# Electret_Microphone_Breakout.net
KiCad netlist of a schematic drawn in EAGLE
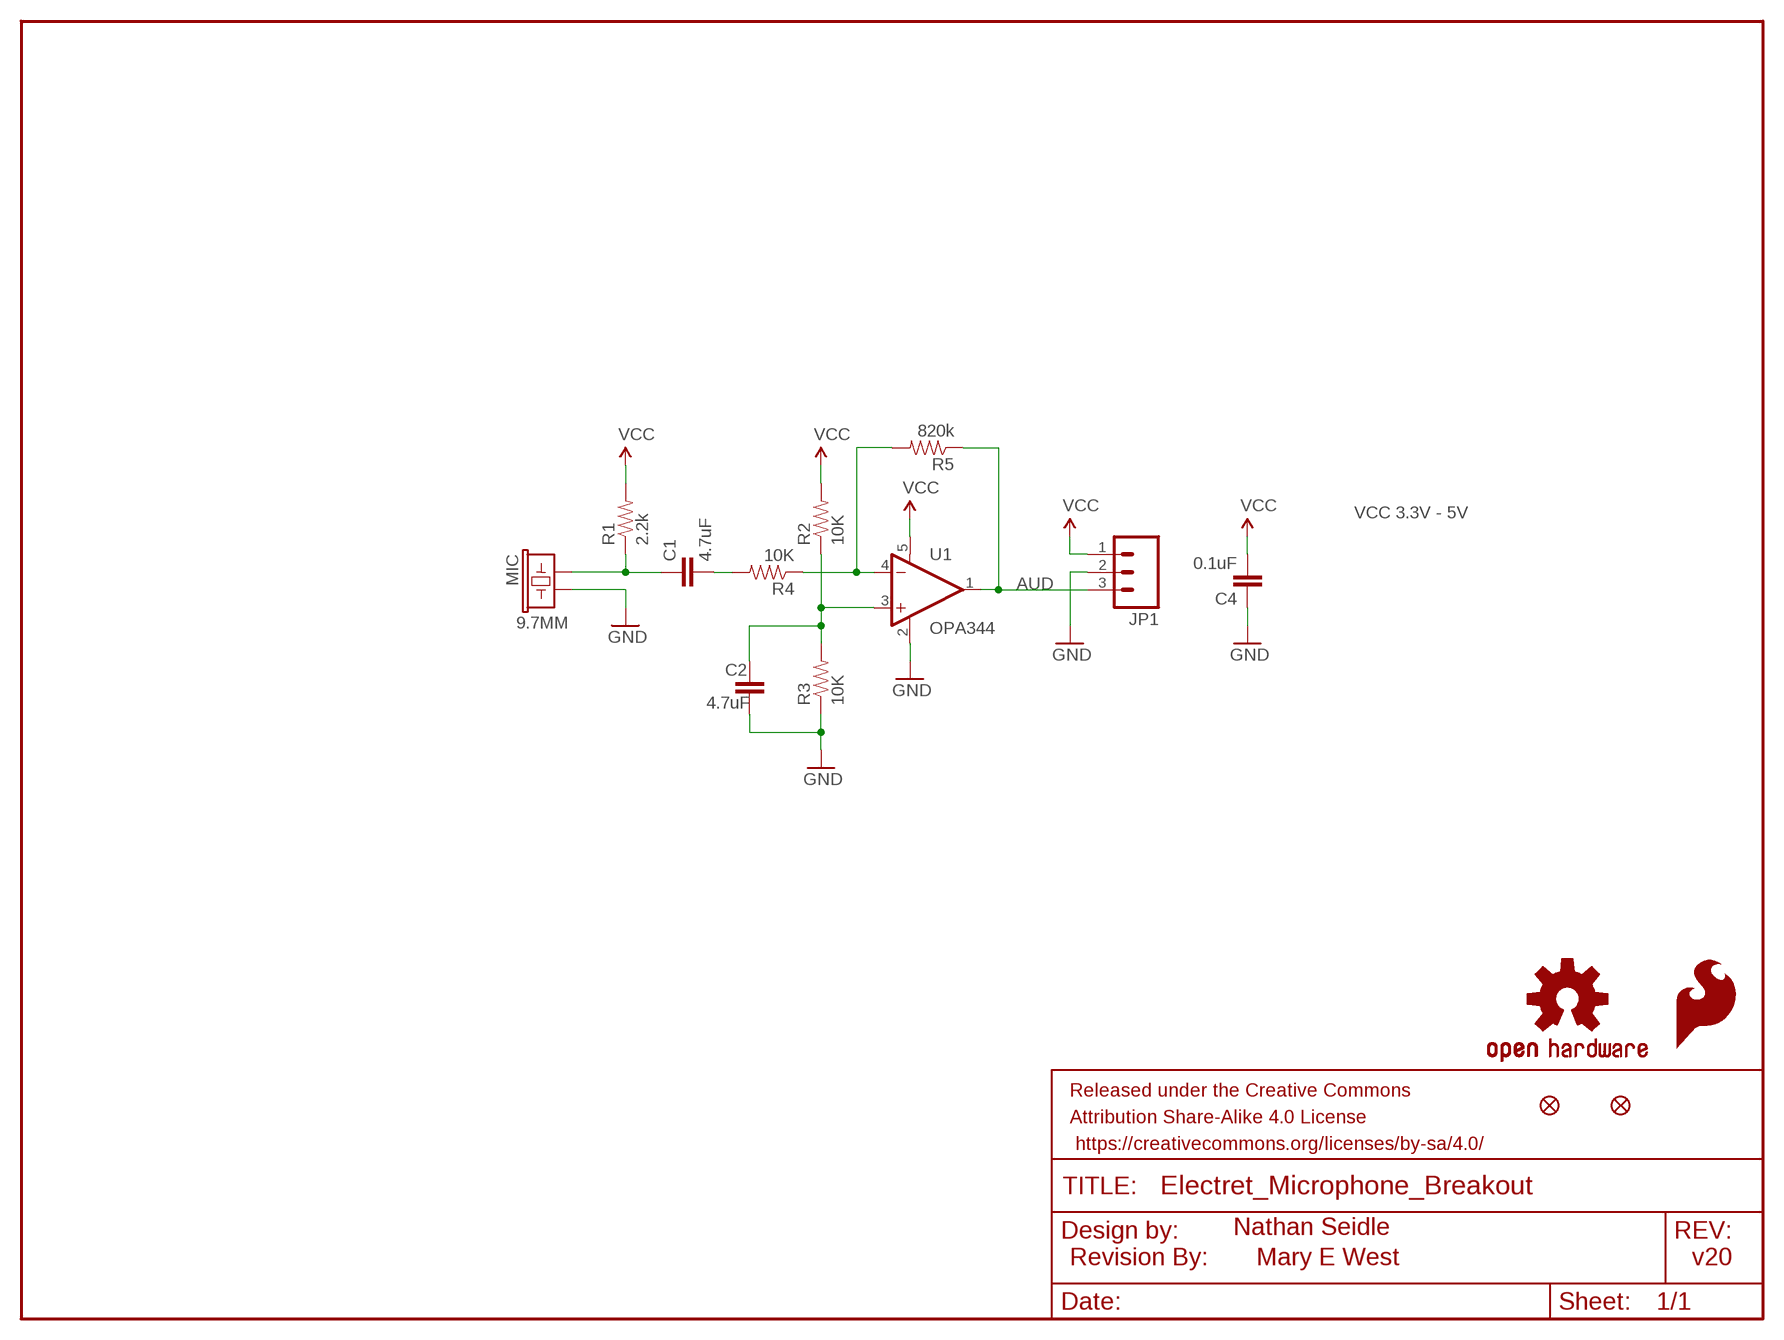
[diagram p0: schematic, sheet 1]

(export (version "E")
  (design (tool "Eeschema 10.0.6"))
  (components
    (comp (ref "C1")
      (value "4.7uF")
      (footprint "eagle-import:0603-CAP")
      (libsource (lib "eagle-import") (part "4.7UF-6.3V-10%(0603)0603"))
    )
    (comp (ref "C2")
      (value "4.7uF")
      (footprint "eagle-import:0603-CAP")
      (libsource (lib "eagle-import") (part "4.7UF-6.3V-10%(0603)0603"))
    )
    (comp (ref "C4")
      (value "0.1uF")
      (footprint "eagle-import:0603-CAP")
      (libsource (lib "eagle-import") (part "0.1UF-25V(+80/-20%)(0603)"))
    )
    (comp (ref "FRAME1")
      (value "FRAME-LETTER")
      (footprint "eagle-import:CREATIVE_COMMONS")
      (libsource (lib "eagle-import") (part "FRAME-LETTER"))
    )
    (comp (ref "JP1")
      (value "M03PTH")
      (footprint "eagle-import:1X03")
      (libsource (lib "eagle-import") (part "M03PTH"))
    )
    (comp (ref "JP2")
      (value "FIDUCIALUFIDUCIAL")
      (footprint "eagle-import:MICRO-FIDUCIAL")
      (libsource (lib "eagle-import") (part "FIDUCIALUFIDUCIAL"))
    )
    (comp (ref "JP3")
      (value "FIDUCIALUFIDUCIAL")
      (footprint "eagle-import:MICRO-FIDUCIAL")
      (libsource (lib "eagle-import") (part "FIDUCIALUFIDUCIAL"))
    )
    (comp (ref "LOGO1")
      (value "OSHW-LOGOMINI")
      (footprint "eagle-import:OSHW-LOGO-MINI")
      (libsource (lib "eagle-import") (part "OSHW-LOGOMINI"))
    )
    (comp (ref "MIC")
      (value "9.7MM")
      (footprint "eagle-import:MIC-9.7MM")
      (libsource (lib "eagle-import") (part "MIC9.7MM"))
    )
    (comp (ref "R1")
      (value "2.2k")
      (footprint "eagle-import:0603-RES")
      (libsource (lib "eagle-import") (part "2.2KOHM-1/10W-1%(0603)"))
    )
    (comp (ref "R2")
      (value "10K")
      (footprint "eagle-import:0603-RES")
      (libsource (lib "eagle-import") (part "10KOHM-1/10W-1%(0603)0603"))
    )
    (comp (ref "R3")
      (value "10K")
      (footprint "eagle-import:0603-RES")
      (libsource (lib "eagle-import") (part "10KOHM-1/10W-1%(0603)0603"))
    )
    (comp (ref "R4")
      (value "10K")
      (footprint "eagle-import:0603-RES")
      (libsource (lib "eagle-import") (part "10KOHM-1/10W-1%(0603)0603"))
    )
    (comp (ref "R5")
      (value "820k")
      (footprint "eagle-import:0603-RES")
      (libsource (lib "eagle-import") (part "820KOHM-1/10W-1%(0603)"))
    )
    (comp (ref "U$1")
      (value "SFE_LOGO_FLAME.1_INCH")
      (footprint "eagle-import:SFE_LOGO_FLAME_.1")
      (libsource (lib "eagle-import") (part "SFE_LOGO_FLAME.1_INCH"))
    )
    (comp (ref "U$2")
      (value "REVISION")
      (footprint "eagle-import:REVISION")
      (libsource (lib "eagle-import") (part "REVISION"))
    )
    (comp (ref "U1")
      (value "OPA344")
      (footprint "eagle-import:SOT23-5")
      (libsource (lib "eagle-import") (part "OPA344"))
    )
  )
  (nets
    (net (code "1") (name "/AUD") (class "Default")
      (node (ref "JP1") (pin "3") (pinfunction "3_3") (pintype "passive"))
      (node (ref "R5") (pin "1") (pinfunction "1_1") (pintype "passive"))
      (node (ref "U1") (pin "1") (pinfunction "OUT_1") (pintype "output"))
    )
    (net (code "2") (name "GND") (class "Default")
      (node (ref "C2") (pin "2") (pinfunction "2_2") (pintype "passive"))
      (node (ref "C4") (pin "1") (pinfunction "1_1") (pintype "passive"))
      (node (ref "JP1") (pin "2") (pinfunction "2_2") (pintype "passive"))
      (node (ref "MIC") (pin "2") (pinfunction "2_2") (pintype "passive"))
      (node (ref "R3") (pin "1") (pinfunction "1_1") (pintype "passive"))
      (node (ref "U1") (pin "2") (pinfunction "V-_2") (pintype "power_in"))
    )
    (net (code "3") (name "Net-(C1-Pad1)") (class "Default")
      (node (ref "C1") (pin "1") (pinfunction "1_1") (pintype "passive"))
      (node (ref "MIC") (pin "1") (pinfunction "1_1") (pintype "passive"))
      (node (ref "R1") (pin "1") (pinfunction "1_1") (pintype "passive"))
    )
    (net (code "4") (name "Net-(C1-Pad2)") (class "Default")
      (node (ref "C1") (pin "2") (pinfunction "2_2") (pintype "passive"))
      (node (ref "R4") (pin "2") (pinfunction "2_2") (pintype "passive"))
    )
    (net (code "5") (name "Net-(U1-+IN)") (class "Default")
      (node (ref "C2") (pin "1") (pinfunction "1_1") (pintype "passive"))
      (node (ref "R2") (pin "1") (pinfunction "1_1") (pintype "passive"))
      (node (ref "R3") (pin "2") (pinfunction "2_2") (pintype "passive"))
      (node (ref "U1") (pin "3") (pinfunction "+IN_3") (pintype "input"))
    )
    (net (code "6") (name "Net-(U1--IN)") (class "Default")
      (node (ref "R4") (pin "1") (pinfunction "1_1") (pintype "passive"))
      (node (ref "R5") (pin "2") (pinfunction "2_2") (pintype "passive"))
      (node (ref "U1") (pin "4") (pinfunction "-IN_4") (pintype "input"))
    )
    (net (code "7") (name "VCC") (class "Default")
      (node (ref "C4") (pin "2") (pinfunction "2_2") (pintype "passive"))
      (node (ref "JP1") (pin "1") (pinfunction "1_1") (pintype "passive"))
      (node (ref "R1") (pin "2") (pinfunction "2_2") (pintype "passive"))
      (node (ref "R2") (pin "2") (pinfunction "2_2") (pintype "passive"))
      (node (ref "U1") (pin "5") (pinfunction "V+_5") (pintype "power_in"))
    )
  )
)
